# MAIN.net
KiCad netlist of a schematic drawn in EAGLE
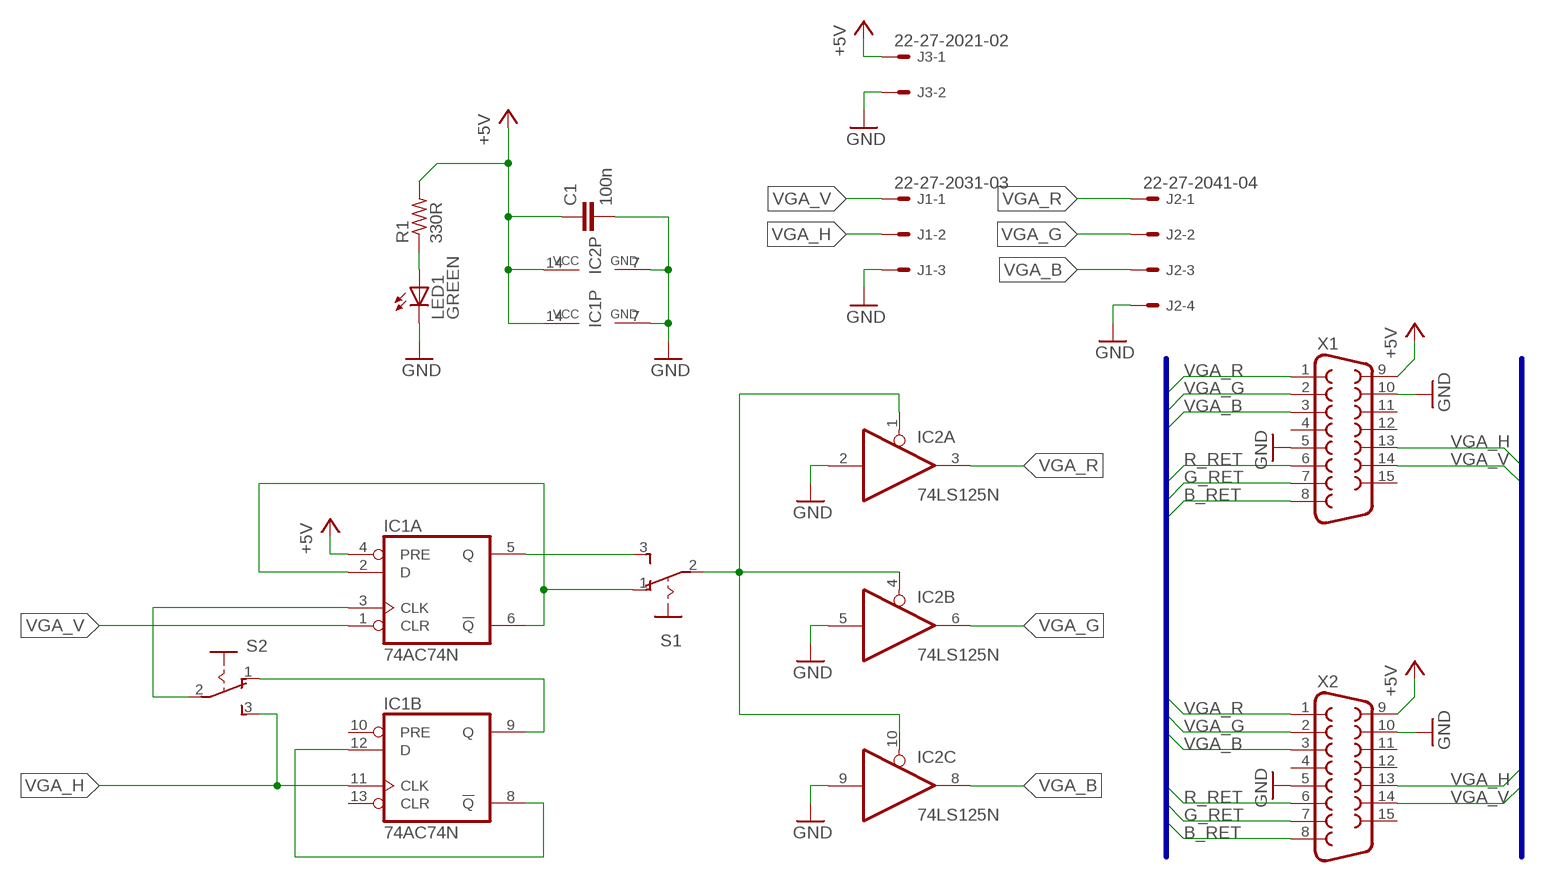
[diagram p0: schematic, sheet 1]

(export (version "E")
  (design (tool "Eeschema 10.0.6"))
  (components
    (comp (ref "C1")
      (value "100n")
      (footprint "eagle-import:C075-032X103")
      (libsource (lib "eagle-import") (part "C-EU075-032X103"))
    )
    (comp (ref "IC1")
      (value "74AC74N")
      (footprint "eagle-import:DIL14")
      (libsource (lib "eagle-import") (part "7474NAC"))
    )
    (comp (ref "IC2")
      (value "74LS125N")
      (footprint "eagle-import:DIL14")
      (libsource (lib "eagle-import") (part "74125NLS"))
    )
    (comp (ref "J1")
      (value "22-27-2031-03")
      (footprint "eagle-import:6410-03")
      (libsource (lib "eagle-import") (part "22-?-0327-2031"))
    )
    (comp (ref "J2")
      (value "22-27-2041-04")
      (footprint "eagle-import:6410-04")
      (libsource (lib "eagle-import") (part "22-?-0427-2041"))
    )
    (comp (ref "J3")
      (value "22-27-2021-02")
      (footprint "eagle-import:6410-02")
      (libsource (lib "eagle-import") (part "22-?-0227-2021"))
    )
    (comp (ref "LED1")
      (value "GREEN")
      (footprint "eagle-import:LED5MM")
      (libsource (lib "eagle-import") (part "LED5MM"))
    )
    (comp (ref "R1")
      (value "330R")
      (footprint "eagle-import:0204_7")
      (libsource (lib "eagle-import") (part "R-US_0204/7"))
    )
    (comp (ref "S1")
      (value "255SB")
      (footprint "eagle-import:255SB")
      (libsource (lib "eagle-import") (part "255SB"))
    )
    (comp (ref "S2")
      (value "255SB")
      (footprint "eagle-import:255SB")
      (libsource (lib "eagle-import") (part "255SB"))
    )
    (comp (ref "X1")
      (value "F15HDH")
      (footprint "eagle-import:HDF15H")
      (libsource (lib "eagle-import") (part "F15HDH"))
    )
    (comp (ref "X2")
      (value "F15HDH")
      (footprint "eagle-import:HDF15H")
      (libsource (lib "eagle-import") (part "F15HDH"))
    )
  )
  (nets
    (net (code "1") (name "+5V") (class "Default")
      (node (ref "C1") (pin "1") (pinfunction "1_1") (pintype "passive"))
      (node (ref "IC1") (pin "14") (pinfunction "VCC_14") (pintype "power_in"))
      (node (ref "IC1") (pin "4") (pinfunction "PRE_4") (pintype "input"))
      (node (ref "IC2") (pin "14") (pinfunction "VCC_14") (pintype "power_in"))
      (node (ref "J3") (pin "1") (pinfunction "S_1") (pintype "passive"))
      (node (ref "R1") (pin "2") (pinfunction "2_2") (pintype "passive"))
      (node (ref "X1") (pin "9") (pinfunction "9_9") (pintype "passive"))
      (node (ref "X2") (pin "9") (pinfunction "9_9") (pintype "passive"))
    )
    (net (code "2") (name "/B_RET") (class "Default")
      (node (ref "X1") (pin "8") (pinfunction "8_8") (pintype "passive"))
      (node (ref "X2") (pin "8") (pinfunction "8_8") (pintype "passive"))
    )
    (net (code "3") (name "/G_RET") (class "Default")
      (node (ref "X1") (pin "7") (pinfunction "7_7") (pintype "passive"))
      (node (ref "X2") (pin "7") (pinfunction "7_7") (pintype "passive"))
    )
    (net (code "4") (name "/R_RET") (class "Default")
      (node (ref "X1") (pin "6") (pinfunction "6_6") (pintype "passive"))
      (node (ref "X2") (pin "6") (pinfunction "6_6") (pintype "passive"))
    )
    (net (code "5") (name "GND") (class "Default")
      (node (ref "C1") (pin "2") (pinfunction "2_2") (pintype "passive"))
      (node (ref "IC1") (pin "7") (pinfunction "GND_7") (pintype "power_in"))
      (node (ref "IC2") (pin "2") (pinfunction "I_2") (pintype "input"))
      (node (ref "IC2") (pin "5") (pinfunction "I_5") (pintype "input"))
      (node (ref "IC2") (pin "7") (pinfunction "GND_7") (pintype "power_in"))
      (node (ref "IC2") (pin "9") (pinfunction "I_9") (pintype "input"))
      (node (ref "J1") (pin "3") (pinfunction "S_3") (pintype "passive"))
      (node (ref "J2") (pin "4") (pinfunction "S_4") (pintype "passive"))
      (node (ref "J3") (pin "2") (pinfunction "S_2") (pintype "passive"))
      (node (ref "LED1") (pin "K") (pinfunction "C_K") (pintype "passive"))
      (node (ref "X1") (pin "10") (pinfunction "10_10") (pintype "passive"))
      (node (ref "X1") (pin "5") (pinfunction "5_5") (pintype "passive"))
      (node (ref "X2") (pin "10") (pinfunction "10_10") (pintype "passive"))
      (node (ref "X2") (pin "5") (pinfunction "5_5") (pintype "passive"))
    )
    (net (code "6") (name "Net-(IC1A-CLK)") (class "Default")
      (node (ref "IC1") (pin "3") (pinfunction "CLK_3") (pintype "input"))
      (node (ref "S2") (pin "2") (pinfunction "P_2") (pintype "passive"))
    )
    (net (code "7") (name "Net-(IC1A-D)") (class "Default")
      (node (ref "IC1") (pin "2") (pinfunction "D_2") (pintype "input"))
      (node (ref "IC1") (pin "6") (pinfunction "~{Q}_6") (pintype "output"))
      (node (ref "S1") (pin "1") (pinfunction "O_1") (pintype "passive"))
    )
    (net (code "8") (name "Net-(IC1A-Q)") (class "Default")
      (node (ref "IC1") (pin "5") (pinfunction "Q_5") (pintype "output"))
      (node (ref "S1") (pin "3") (pinfunction "S_3") (pintype "passive"))
    )
    (net (code "9") (name "Net-(IC1B-D)") (class "Default")
      (node (ref "IC1") (pin "12") (pinfunction "D_12") (pintype "input"))
      (node (ref "IC1") (pin "8") (pinfunction "~{Q}_8") (pintype "output"))
    )
    (net (code "10") (name "Net-(IC1B-Q)") (class "Default")
      (node (ref "IC1") (pin "9") (pinfunction "Q_9") (pintype "output"))
      (node (ref "S2") (pin "1") (pinfunction "O_1") (pintype "passive"))
    )
    (net (code "11") (name "Net-(IC2A-OE)") (class "Default")
      (node (ref "IC2") (pin "1") (pinfunction "OE_1") (pintype "input"))
      (node (ref "IC2") (pin "10") (pinfunction "OE_10") (pintype "input"))
      (node (ref "IC2") (pin "4") (pinfunction "OE_4") (pintype "input"))
      (node (ref "S1") (pin "2") (pinfunction "P_2") (pintype "passive"))
    )
    (net (code "12") (name "Net-(LED1-PadA)") (class "Default")
      (node (ref "LED1") (pin "A") (pinfunction "A_A") (pintype "passive"))
      (node (ref "R1") (pin "1") (pinfunction "1_1") (pintype "passive"))
    )
    (net (code "13") (name "VGA_B") (class "Default")
      (node (ref "IC2") (pin "8") (pinfunction "O_8") (pintype "tri_state"))
      (node (ref "J2") (pin "3") (pinfunction "S_3") (pintype "passive"))
      (node (ref "X1") (pin "3") (pinfunction "3_3") (pintype "passive"))
      (node (ref "X2") (pin "3") (pinfunction "3_3") (pintype "passive"))
    )
    (net (code "14") (name "VGA_G") (class "Default")
      (node (ref "IC2") (pin "6") (pinfunction "O_6") (pintype "tri_state"))
      (node (ref "J2") (pin "2") (pinfunction "S_2") (pintype "passive"))
      (node (ref "X1") (pin "2") (pinfunction "2_2") (pintype "passive"))
      (node (ref "X2") (pin "2") (pinfunction "2_2") (pintype "passive"))
    )
    (net (code "15") (name "VGA_H") (class "Default")
      (node (ref "IC1") (pin "11") (pinfunction "CLK_11") (pintype "input"))
      (node (ref "J1") (pin "2") (pinfunction "S_2") (pintype "passive"))
      (node (ref "S2") (pin "3") (pinfunction "S_3") (pintype "passive"))
      (node (ref "X1") (pin "13") (pinfunction "13_13") (pintype "passive"))
      (node (ref "X2") (pin "13") (pinfunction "13_13") (pintype "passive"))
    )
    (net (code "16") (name "VGA_R") (class "Default")
      (node (ref "IC2") (pin "3") (pinfunction "O_3") (pintype "tri_state"))
      (node (ref "J2") (pin "1") (pinfunction "S_1") (pintype "passive"))
      (node (ref "X1") (pin "1") (pinfunction "1_1") (pintype "passive"))
      (node (ref "X2") (pin "1") (pinfunction "1_1") (pintype "passive"))
    )
    (net (code "17") (name "VGA_V") (class "Default")
      (node (ref "IC1") (pin "1") (pinfunction "CLR_1") (pintype "input"))
      (node (ref "J1") (pin "1") (pinfunction "S_1") (pintype "passive"))
      (node (ref "X1") (pin "14") (pinfunction "14_14") (pintype "passive"))
      (node (ref "X2") (pin "14") (pinfunction "14_14") (pintype "passive"))
    )
    (net (code "18") (name "unconnected-(IC1B-CLR-Pad13)") (class "Default")
      (node (ref "IC1") (pin "13") (pinfunction "CLR_13") (pintype "input"))
    )
    (net (code "19") (name "unconnected-(IC1B-PRE-Pad10)") (class "Default")
      (node (ref "IC1") (pin "10") (pinfunction "PRE_10") (pintype "input"))
    )
    (net (code "20") (name "unconnected-(X1-Pad4)") (class "Default")
      (node (ref "X1") (pin "4") (pinfunction "4_4") (pintype "passive"))
    )
    (net (code "21") (name "unconnected-(X1-Pad11)") (class "Default")
      (node (ref "X1") (pin "11") (pinfunction "11_11") (pintype "passive"))
    )
    (net (code "22") (name "unconnected-(X1-Pad12)") (class "Default")
      (node (ref "X1") (pin "12") (pinfunction "12_12") (pintype "passive"))
    )
    (net (code "23") (name "unconnected-(X1-Pad15)") (class "Default")
      (node (ref "X1") (pin "15") (pinfunction "15_15") (pintype "passive"))
    )
    (net (code "24") (name "unconnected-(X2-Pad4)") (class "Default")
      (node (ref "X2") (pin "4") (pinfunction "4_4") (pintype "passive"))
    )
    (net (code "25") (name "unconnected-(X2-Pad11)") (class "Default")
      (node (ref "X2") (pin "11") (pinfunction "11_11") (pintype "passive"))
    )
    (net (code "26") (name "unconnected-(X2-Pad12)") (class "Default")
      (node (ref "X2") (pin "12") (pinfunction "12_12") (pintype "passive"))
    )
    (net (code "27") (name "unconnected-(X2-Pad15)") (class "Default")
      (node (ref "X2") (pin "15") (pinfunction "15_15") (pintype "passive"))
    )
  )
)
